# Sheet1.net
KiCad netlist of a schematic drawn in Altium Designer
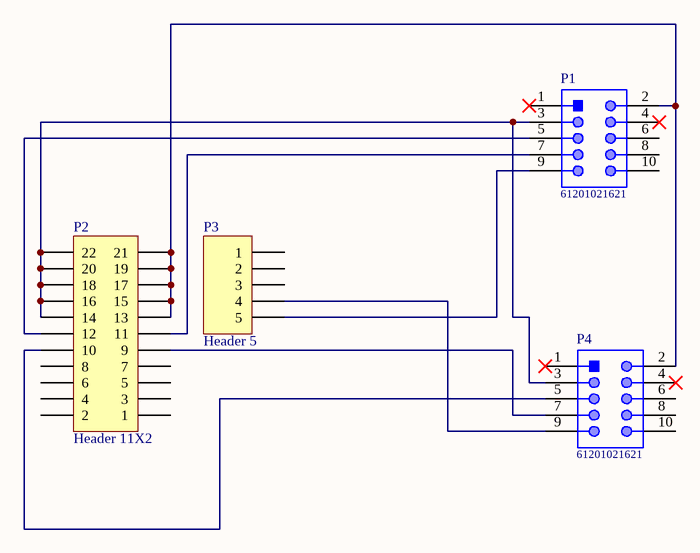
[diagram p0: Sheet1.SchDoc]

(export (version "E")
  (design (tool "Eeschema 10.0.6"))
  (components
    (comp (ref "P1")
      (value "61201021621")
      (footprint "61201021621")
      (description "Male Box Header WR-BHD, THT, Vertical, pitch 2.54 mm, 10 pins")
      (fields (field (name "MANUFACTURER") "Wurth Elektronik") (field (name "PUBLISHER") "WurthElektronik"))
      (libsource (lib "Altium Content Vault") (part "WE-CN-2P-M-R10"))
    )
    (comp (ref "P2")
      (value "Header 11X2")
      (footprint "HDR2X11")
      (description "Header, 11-Pin, Dual row")
      (fields (field (name "PUBLISHER") "Altium Limited"))
      (libsource (lib "Miscellaneous Connectors") (part "Header 11X2"))
    )
    (comp (ref "P3")
      (value "Header 5")
      (footprint "HDR1X5")
      (description "Header, 5-Pin")
      (fields (field (name "PUBLISHER") "Altium Limited"))
      (libsource (lib "Miscellaneous Connectors") (part "Header 5"))
    )
    (comp (ref "P4")
      (value "61201021621")
      (footprint "61201021621")
      (description "Male Box Header WR-BHD, THT, Vertical, pitch 2.54 mm, 10 pins")
      (fields (field (name "MANUFACTURER") "Wurth Elektronik") (field (name "PUBLISHER") "WurthElektronik"))
      (libsource (lib "Altium Content Vault") (part "WE-CN-2P-M-R10"))
    )
  )
  (nets
    (net (code "1") (name "Net-(P1-Pad2)") (class "Default")
      (node (ref "P1") (pin "2") (pinfunction "2_2") (pintype "passive"))
      (node (ref "P2") (pin "13") (pinfunction "13_13") (pintype "passive"))
      (node (ref "P2") (pin "15") (pinfunction "15_15") (pintype "passive"))
      (node (ref "P2") (pin "17") (pinfunction "17_17") (pintype "passive"))
      (node (ref "P2") (pin "19") (pinfunction "19_19") (pintype "passive"))
      (node (ref "P2") (pin "21") (pinfunction "21_21") (pintype "passive"))
      (node (ref "P4") (pin "2") (pinfunction "2_2") (pintype "passive"))
    )
    (net (code "2") (name "Net-(P1-Pad3)") (class "Default")
      (node (ref "P1") (pin "3") (pinfunction "3_3") (pintype "passive"))
      (node (ref "P2") (pin "14") (pinfunction "14_14") (pintype "passive"))
      (node (ref "P2") (pin "16") (pinfunction "16_16") (pintype "passive"))
      (node (ref "P2") (pin "18") (pinfunction "18_18") (pintype "passive"))
      (node (ref "P2") (pin "20") (pinfunction "20_20") (pintype "passive"))
      (node (ref "P2") (pin "22") (pinfunction "22_22") (pintype "passive"))
      (node (ref "P4") (pin "3") (pinfunction "3_3") (pintype "passive"))
    )
    (net (code "3") (name "Net-(P1-Pad5)") (class "Default")
      (node (ref "P1") (pin "5") (pinfunction "5_5") (pintype "passive"))
      (node (ref "P2") (pin "12") (pinfunction "12_12") (pintype "passive"))
    )
    (net (code "4") (name "Net-(P1-Pad7)") (class "Default")
      (node (ref "P1") (pin "7") (pinfunction "7_7") (pintype "passive"))
      (node (ref "P2") (pin "11") (pinfunction "11_11") (pintype "passive"))
    )
    (net (code "5") (name "Net-(P1-Pad9)") (class "Default")
      (node (ref "P1") (pin "9") (pinfunction "9_9") (pintype "passive"))
      (node (ref "P3") (pin "5") (pinfunction "5_5") (pintype "passive"))
    )
    (net (code "6") (name "Net-(P2-Pad9)") (class "Default")
      (node (ref "P2") (pin "9") (pinfunction "9_9") (pintype "passive"))
      (node (ref "P4") (pin "7") (pinfunction "7_7") (pintype "passive"))
    )
    (net (code "7") (name "Net-(P2-Pad10)") (class "Default")
      (node (ref "P2") (pin "10") (pinfunction "10_10") (pintype "passive"))
      (node (ref "P4") (pin "5") (pinfunction "5_5") (pintype "passive"))
    )
    (net (code "8") (name "Net-(P3-Pad4)") (class "Default")
      (node (ref "P3") (pin "4") (pinfunction "4_4") (pintype "passive"))
      (node (ref "P4") (pin "9") (pinfunction "9_9") (pintype "passive"))
    )
    (net (code "9") (name "unconnected-(P1-Pad1)") (class "Default")
      (node (ref "P1") (pin "1") (pinfunction "1_1") (pintype "passive+no_connect"))
    )
    (net (code "10") (name "unconnected-(P1-Pad4)") (class "Default")
      (node (ref "P1") (pin "4") (pinfunction "4_4") (pintype "passive+no_connect"))
    )
    (net (code "11") (name "unconnected-(P1-Pad6)") (class "Default")
      (node (ref "P1") (pin "6") (pinfunction "6_6") (pintype "passive"))
    )
    (net (code "12") (name "unconnected-(P1-Pad8)") (class "Default")
      (node (ref "P1") (pin "8") (pinfunction "8_8") (pintype "passive"))
    )
    (net (code "13") (name "unconnected-(P1-Pad10)") (class "Default")
      (node (ref "P1") (pin "10") (pinfunction "10_10") (pintype "passive"))
    )
    (net (code "14") (name "unconnected-(P2-Pad1)") (class "Default")
      (node (ref "P2") (pin "1") (pinfunction "1_1") (pintype "passive"))
    )
    (net (code "15") (name "unconnected-(P2-Pad2)") (class "Default")
      (node (ref "P2") (pin "2") (pinfunction "2_2") (pintype "passive"))
    )
    (net (code "16") (name "unconnected-(P2-Pad3)") (class "Default")
      (node (ref "P2") (pin "3") (pinfunction "3_3") (pintype "passive"))
    )
    (net (code "17") (name "unconnected-(P2-Pad4)") (class "Default")
      (node (ref "P2") (pin "4") (pinfunction "4_4") (pintype "passive"))
    )
    (net (code "18") (name "unconnected-(P2-Pad5)") (class "Default")
      (node (ref "P2") (pin "5") (pinfunction "5_5") (pintype "passive"))
    )
    (net (code "19") (name "unconnected-(P2-Pad6)") (class "Default")
      (node (ref "P2") (pin "6") (pinfunction "6_6") (pintype "passive"))
    )
    (net (code "20") (name "unconnected-(P2-Pad7)") (class "Default")
      (node (ref "P2") (pin "7") (pinfunction "7_7") (pintype "passive"))
    )
    (net (code "21") (name "unconnected-(P2-Pad8)") (class "Default")
      (node (ref "P2") (pin "8") (pinfunction "8_8") (pintype "passive"))
    )
    (net (code "22") (name "unconnected-(P3-Pad1)") (class "Default")
      (node (ref "P3") (pin "1") (pinfunction "1_1") (pintype "passive"))
    )
    (net (code "23") (name "unconnected-(P3-Pad2)") (class "Default")
      (node (ref "P3") (pin "2") (pinfunction "2_2") (pintype "passive"))
    )
    (net (code "24") (name "unconnected-(P3-Pad3)") (class "Default")
      (node (ref "P3") (pin "3") (pinfunction "3_3") (pintype "passive"))
    )
    (net (code "25") (name "unconnected-(P4-Pad1)") (class "Default")
      (node (ref "P4") (pin "1") (pinfunction "1_1") (pintype "passive+no_connect"))
    )
    (net (code "26") (name "unconnected-(P4-Pad4)") (class "Default")
      (node (ref "P4") (pin "4") (pinfunction "4_4") (pintype "passive+no_connect"))
    )
    (net (code "27") (name "unconnected-(P4-Pad6)") (class "Default")
      (node (ref "P4") (pin "6") (pinfunction "6_6") (pintype "passive"))
    )
    (net (code "28") (name "unconnected-(P4-Pad8)") (class "Default")
      (node (ref "P4") (pin "8") (pinfunction "8_8") (pintype "passive"))
    )
    (net (code "29") (name "unconnected-(P4-Pad10)") (class "Default")
      (node (ref "P4") (pin "10") (pinfunction "10_10") (pintype "passive"))
    )
  )
)
